# SourceOptode.net
KiCad netlist of a schematic drawn in Altium Designer
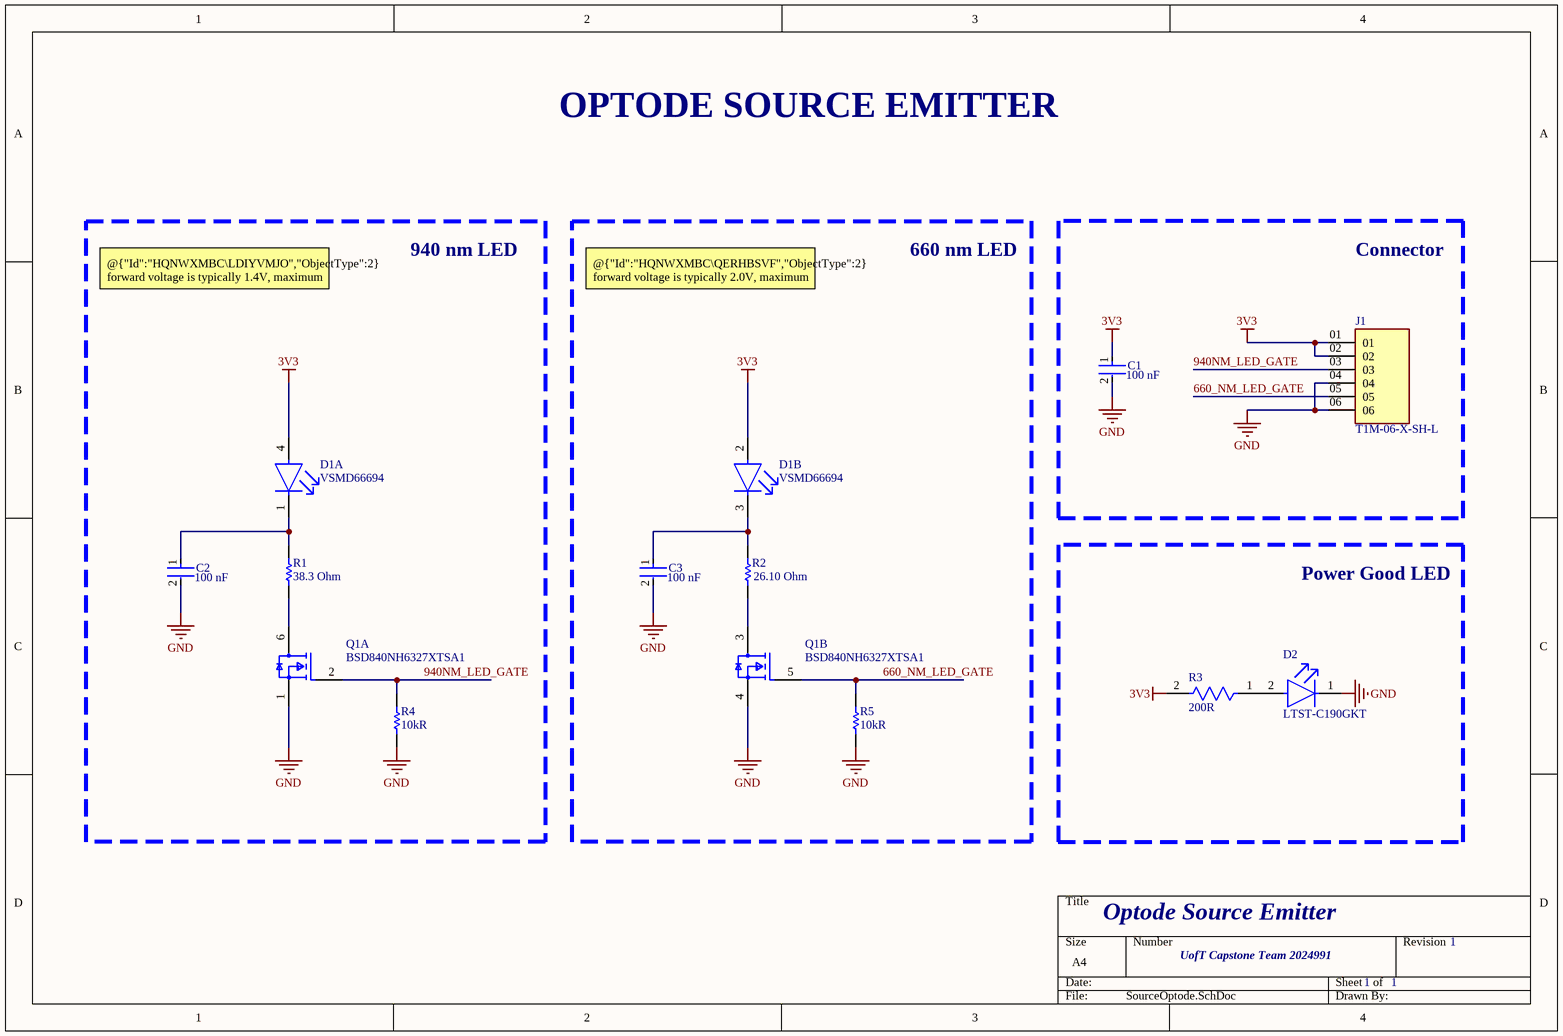
[diagram p0: SourceOptode.SchDoc]

(export (version "E")
  (design (tool "Eeschema 10.0.6"))
  (components
    (comp (ref "C1")
      (value "CC0603KRX7R7BB104")
      (footprint "FP-CC0603-DA-MFG")
      (description "CAP CER 0.1UF 16V X7R 0603")
      (fields
        (field (name "OCTOPART") "https://octopart.com/cc0603krx7r7bb104-yageo-192941")
        (field (name "TOLERANCE") "0.1")
        (field (name "CAPACITANCE") "100 nF")
      )
      (libsource (lib "Altium Content Vault") (part "11868f565c42a9108669ba33697ecf6"))
    )
    (comp (ref "C2")
      (value "CC0603KRX7R7BB104")
      (footprint "FP-CC0603-DA-MFG")
      (description "CAP CER 0.1UF 16V X7R 0603")
      (fields
        (field (name "OCTOPART") "https://octopart.com/cc0603krx7r7bb104-yageo-192941")
        (field (name "TOLERANCE") "0.1")
        (field (name "CAPACITANCE") "100 nF")
      )
      (libsource (lib "Altium Content Vault") (part "11868f565c42a9108669ba33697ecf6"))
    )
    (comp (ref "C3")
      (value "CC0603KRX7R7BB104")
      (footprint "FP-CC0603-DA-MFG")
      (description "CAP CER 0.1UF 16V X7R 0603")
      (fields
        (field (name "OCTOPART") "https://octopart.com/cc0603krx7r7bb104-yageo-192941")
        (field (name "TOLERANCE") "0.1")
        (field (name "CAPACITANCE") "100 nF")
      )
      (libsource (lib "Altium Content Vault") (part "11868f565c42a9108669ba33697ecf6"))
    )
    (comp (ref "D1")
      (value "VSMD66694")
      (footprint "FP-6_550-5347_01-4-MFG")
      (description "EMITTER DUAL 660/940NM SQURE PCB")
      (fields
        (field (name "MANUFACTURER") "Vishay Semiconductor Opto Division")
        (field (name "OCTOPART") "https://octopart.com/vsmd66694-vishay-74221794")
      )
      (libsource (lib "Altium Content Vault") (part "f63fdef09506549d47f9c99805bef80"))
    )
    (comp (ref "D2")
      (value "LTST-C190GKT")
      (footprint "FP-LTST-C190GKT-MFG")
      (description "LED GREEN CLEAR CHIP SMD")
      (fields (field (name "VOLTAGE") "2V"))
      (libsource (lib "Altium Content Vault") (part "8706943c75ba83719d021d2fdc84c58"))
    )
    (comp (ref "J1")
      (value "T1M-06-X-SH-L")
      (footprint "SAMTEC_T1M-06-X-SH-L")
      (description "Connector Header Surface Mount, Right Angle 6 position 0.039\" (1.00mm)")
      (fields (field (name "MF") "Samtec"))
      (libsource (lib "Schlib1") (part "T1M-06-X-SH-L"))
    )
    (comp (ref "Q1")
      (value "BSD840NH6327XTSA1")
      (footprint "FP-PG-SOT363-6-MFG")
      (description "MOSFET 2N-CH 20V 0.88A SOT363")
      (libsource (lib "Altium Content Vault") (part "6559164231102c4ec4f565336d3f230"))
    )
    (comp (ref "R1")
      (value "RK73H1JTTD38R3F")
      (footprint "RESC1608X55X30LL20T10")
      (fields (field (name "MANUFACTURER") "KOA Speer") (field (name "RESISTANCE") "38.3 Ohm"))
      (libsource (lib "Altium Content Vault") (part "RES"))
    )
    (comp (ref "R2")
      (value "26.10 Ohm")
      (footprint "RESC0603(1608)_L")
      (description "26R1 0.1W 1% 0603 (1608 Metric)  SMD")
      (fields (field (name "POWER") "0.1 W") (field (name "TOLERANCE") "1 %"))
      (libsource (lib "Altium Content Vault") (part "RES"))
    )
    (comp (ref "R3")
      (value "CRCW0603200RFKEA")
      (footprint "FP-CRCW0603-e3-MFG")
      (description "RES Thick Film, 200Ω, 1%, 0.1W, 100ppm/°C, 0603")
      (fields (field (name "TOLERANCE") "1%") (field (name "RESISTANCE") "200R"))
      (libsource (lib "Altium Content Vault") (part "1029c3af85768c4190bb7ad29bc67b5"))
    )
    (comp (ref "R4")
      (value "CRCW060310K0FKEA")
      (footprint "RESC1609X50X30NL8T20")
      (description "Chip Resistor, 10 KOhm, +/- 1%, 100 mW, -55 to 155 degC, 0603 (1608 Metric), RoHS, Tape and Reel")
      (fields (field (name "MANUFACTURER") "Vishay Semiconductor") (field (name "RESISTANCE") "10kR"))
      (libsource (lib "Altium Content Vault") (part "RES-2"))
    )
    (comp (ref "R5")
      (value "CRCW060310K0FKEA")
      (footprint "RESC1609X50X30NL8T20")
      (description "Chip Resistor, 10 KOhm, +/- 1%, 100 mW, -55 to 155 degC, 0603 (1608 Metric), RoHS, Tape and Reel")
      (fields (field (name "MANUFACTURER") "Vishay Semiconductor") (field (name "RESISTANCE") "10kR"))
      (libsource (lib "Altium Content Vault") (part "RES-2"))
    )
  )
  (nets
    (net (code "1") (name "/660_NM_LED_GATE") (class "Default")
      (node (ref "J1") (pin "05") (pinfunction "05_05") (pintype "passive"))
      (node (ref "Q1") (pin "5") (pinfunction "2_GATE_5") (pintype "passive"))
      (node (ref "R5") (pin "2") (pinfunction "2_2") (pintype "passive"))
    )
    (net (code "2") (name "/940NM_LED_GATE") (class "Default")
      (node (ref "J1") (pin "03") (pinfunction "03_03") (pintype "passive"))
      (node (ref "Q1") (pin "2") (pinfunction "1_GATE_2") (pintype "passive"))
      (node (ref "R4") (pin "2") (pinfunction "2_2") (pintype "passive"))
    )
    (net (code "3") (name "3V3") (class "Default")
      (node (ref "C1") (pin "1") (pinfunction "1_1") (pintype "passive"))
      (node (ref "D1") (pin "2") (pinfunction "RED_A_2") (pintype "passive"))
      (node (ref "D1") (pin "4") (pinfunction "IR_anode_4") (pintype "passive"))
      (node (ref "J1") (pin "01") (pinfunction "01_01") (pintype "passive"))
      (node (ref "J1") (pin "02") (pinfunction "02_02") (pintype "passive"))
      (node (ref "R3") (pin "2") (pinfunction "2_2") (pintype "passive"))
    )
    (net (code "4") (name "GND") (class "Default")
      (node (ref "C1") (pin "2") (pinfunction "2_2") (pintype "passive"))
      (node (ref "C2") (pin "2") (pinfunction "2_2") (pintype "passive"))
      (node (ref "C3") (pin "2") (pinfunction "2_2") (pintype "passive"))
      (node (ref "D2") (pin "1") (pinfunction "C_1") (pintype "passive"))
      (node (ref "J1") (pin "04") (pinfunction "04_04") (pintype "passive"))
      (node (ref "J1") (pin "06") (pinfunction "06_06") (pintype "passive"))
      (node (ref "Q1") (pin "1") (pinfunction "1_SOURCE_1") (pintype "passive"))
      (node (ref "Q1") (pin "4") (pinfunction "2_SOURCE_4") (pintype "passive"))
      (node (ref "R4") (pin "1") (pinfunction "1_1") (pintype "passive"))
      (node (ref "R5") (pin "1") (pinfunction "1_1") (pintype "passive"))
    )
    (net (code "5") (name "Net-(D1A-IR_cathode)") (class "Default")
      (node (ref "C2") (pin "1") (pinfunction "1_1") (pintype "passive"))
      (node (ref "D1") (pin "1") (pinfunction "IR_cathode_1") (pintype "passive"))
      (node (ref "R1") (pin "2") (pinfunction "2_2") (pintype "passive"))
    )
    (net (code "6") (name "Net-(D1B-RED_C)") (class "Default")
      (node (ref "C3") (pin "1") (pinfunction "1_1") (pintype "passive"))
      (node (ref "D1") (pin "3") (pinfunction "RED_C_3") (pintype "passive"))
      (node (ref "R2") (pin "2") (pinfunction "2_2") (pintype "passive"))
    )
    (net (code "7") (name "Net-(D2-A)") (class "Default")
      (node (ref "D2") (pin "2") (pinfunction "A_2") (pintype "passive"))
      (node (ref "R3") (pin "1") (pinfunction "1_1") (pintype "passive"))
    )
    (net (code "8") (name "Net-(Q1A-1_DRAIN)") (class "Default")
      (node (ref "Q1") (pin "6") (pinfunction "1_DRAIN_6") (pintype "passive"))
      (node (ref "R1") (pin "1") (pinfunction "1_1") (pintype "passive"))
    )
    (net (code "9") (name "Net-(Q1B-2_DRAIN)") (class "Default")
      (node (ref "Q1") (pin "3") (pinfunction "2_DRAIN_3") (pintype "passive"))
      (node (ref "R2") (pin "1") (pinfunction "1_1") (pintype "passive"))
    )
  )
)
